# LED.net
KiCad netlist of a schematic drawn in Altium Designer
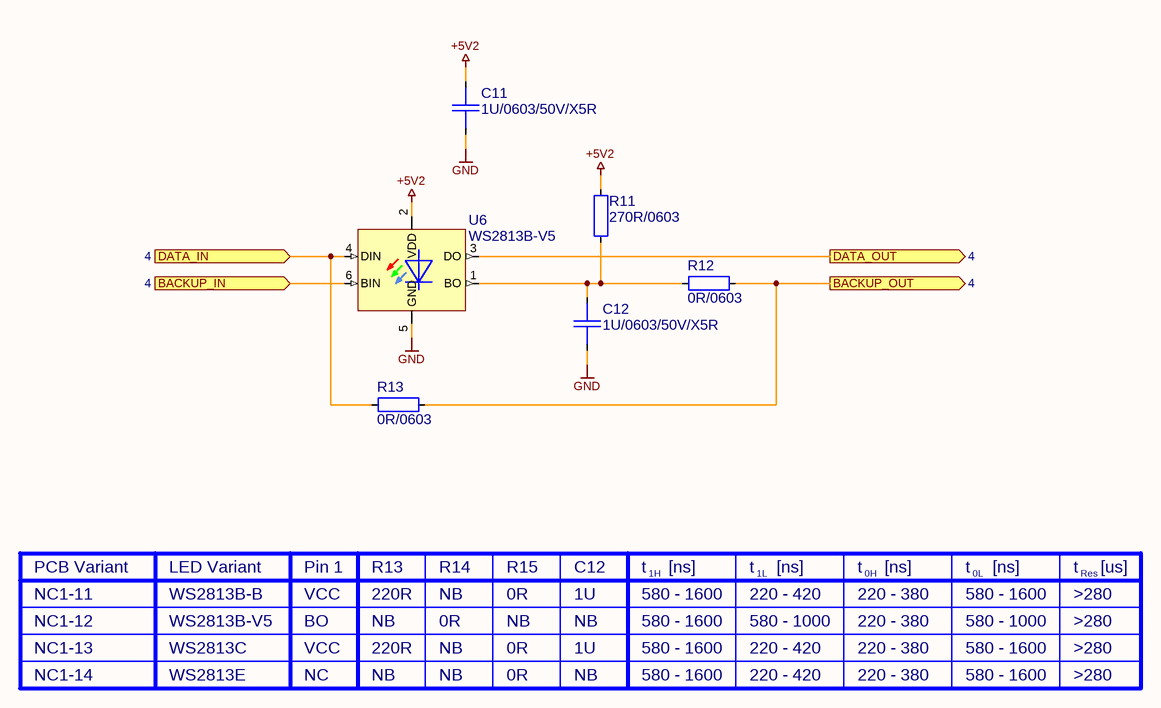
[diagram p0: LED.SchDoc]

(export (version "E")
  (design (tool "Eeschema 10.0.6"))
  (components
    (comp (ref "C11")
      (value "1U/0603/50V/X5R")
      (footprint "CAP0603_X7R")
      (description "CAP SM 0603 1.0uF 50V X5R")
      (fields (field (name "MANUFACTURER") "GENERIC"))
      (libsource (lib "daniw_altium_lib") (part "C"))
    )
    (comp (ref "C12")
      (value "1U/0603/50V/X5R")
      (footprint "CAP0603_X7R")
      (description "CAP SM 0603 1.0uF 50V X5R")
      (fields (field (name "MANUFACTURER") "GENERIC"))
      (libsource (lib "daniw_altium_lib") (part "C"))
    )
    (comp (ref "R11")
      (value "270R/0603")
      (footprint "R0603-0.40-WW")
      (description "RES SM 0603 270R")
      (fields (field (name "MANUFACTURER") "GENERIC"))
      (libsource (lib "daniw_altium_lib") (part "R"))
    )
    (comp (ref "R12")
      (value "0R/0603")
      (footprint "R0603-0.40-WW")
      (description "RES SM 0603 0R")
      (fields (field (name "MANUFACTURER") "GENERIC"))
      (libsource (lib "daniw_altium_lib") (part "R"))
    )
    (comp (ref "R13")
      (value "0R/0603")
      (footprint "R0603-0.40-WW")
      (description "RES SM 0603 0R")
      (fields (field (name "MANUFACTURER") "GENERIC"))
      (libsource (lib "daniw_altium_lib") (part "R"))
    )
    (comp (ref "U6")
      (value "WS2813B-V5")
      (footprint "LEDM5050X165-6-SE")
      (description "Intelligent control LED integrated light source with backup Pin")
      (fields (field (name "MANUFACTURER") "WorldSemi"))
      (libsource (lib "daniw_altium_lib") (part "WS2813_BO"))
    )
  )
  (nets
    (net (code "1") (name "+5V2") (class "Default")
      (node (ref "C11") (pin "1") (pinfunction "1_1") (pintype "passive"))
      (node (ref "R11") (pin "1") (pinfunction "1_1") (pintype "passive"))
      (node (ref "U6") (pin "2") (pinfunction "VDD_2") (pintype "passive"))
    )
    (net (code "2") (name "/BACKUP_IN") (class "Default")
      (node (ref "U6") (pin "6") (pinfunction "BIN_6") (pintype "input"))
    )
    (net (code "3") (name "/BACKUP_OUT") (class "Default")
      (node (ref "R12") (pin "2") (pinfunction "2_2") (pintype "passive"))
      (node (ref "R13") (pin "2") (pinfunction "2_2") (pintype "passive"))
    )
    (net (code "4") (name "/DATA_IN") (class "Default")
      (node (ref "R13") (pin "1") (pinfunction "1_1") (pintype "passive"))
      (node (ref "U6") (pin "4") (pinfunction "DIN_4") (pintype "input"))
    )
    (net (code "5") (name "/DATA_OUT") (class "Default")
      (node (ref "U6") (pin "3") (pinfunction "DO_3") (pintype "output"))
    )
    (net (code "6") (name "GND") (class "Default")
      (node (ref "C11") (pin "2") (pinfunction "2_2") (pintype "passive"))
      (node (ref "C12") (pin "2") (pinfunction "2_2") (pintype "passive"))
      (node (ref "U6") (pin "5") (pinfunction "GND_5") (pintype "passive"))
    )
    (net (code "7") (name "Net-(U6-BO)") (class "Default")
      (node (ref "C12") (pin "1") (pinfunction "1_1") (pintype "passive"))
      (node (ref "R11") (pin "2") (pinfunction "2_2") (pintype "passive"))
      (node (ref "R12") (pin "1") (pinfunction "1_1") (pintype "passive"))
      (node (ref "U6") (pin "1") (pinfunction "BO_1") (pintype "output"))
    )
  )
)
